# 555_Astable_Multivibrator.net
KiCad netlist of a schematic drawn in Altium Designer
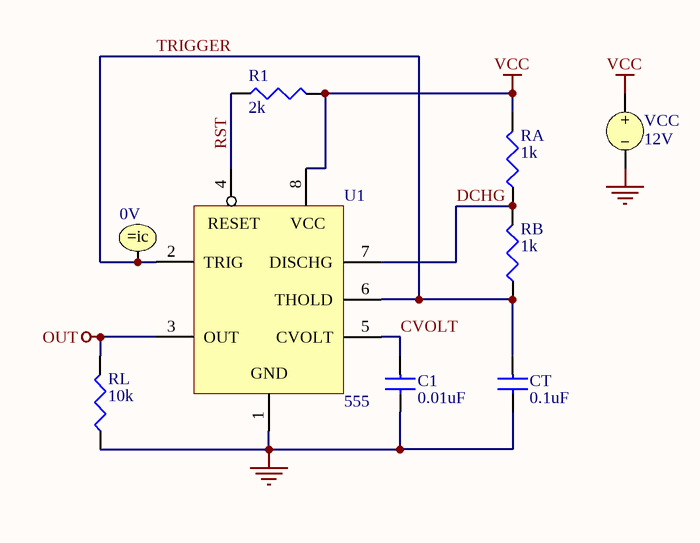
[diagram p0: 555 Astable Multivibrator.schdoc]

(export (version "E")
  (design (tool "Eeschema 10.0.6"))
  (components
    (comp (ref "C1") (value "0.01uF") (description "Capacitor") (libsource (lib "*") (part "CAP")))
    (comp (ref "CT") (value "0.1uF") (description "Capacitor") (libsource (lib "*") (part "CAP")))
    (comp (ref "IC1")
      (value "0V")
      (description "Initial Condition")
      (fields (field (name "INITIAL VOLTAGE") "0V"))
      (libsource (lib "*") (part ".IC"))
    )
    (comp (ref "R1") (value "2k") (description "Resistor") (libsource (lib "*") (part "RES")))
    (comp (ref "RA") (value "1k") (description "Resistor") (libsource (lib "") (part "RES_1")))
    (comp (ref "RB") (value "1k") (description "Resistor") (libsource (lib "") (part "RES_1")))
    (comp (ref "RL") (value "10k") (description "Resistor") (libsource (lib "") (part "RES_1")))
    (comp (ref "U1") (value "555") (description "Timer") (libsource (lib "*") (part "555")))
    (comp (ref "VCC") (value "12V") (description "Voltage Source") (libsource (lib "*") (part "VSRC")))
  )
  (nets
    (net (code "1") (name "/CVOLT") (class "Default")
      (node (ref "C1") (pin "1") (pinfunction "1_1") (pintype "passive"))
      (node (ref "U1") (pin "5") (pinfunction "CVOLT_5") (pintype "passive"))
    )
    (net (code "2") (name "/DCHG") (class "Default")
      (node (ref "RA") (pin "2") (pinfunction "BOT_2") (pintype "passive"))
      (node (ref "RB") (pin "1") (pinfunction "TOP_1") (pintype "passive"))
      (node (ref "U1") (pin "7") (pinfunction "DISCHG_7") (pintype "passive"))
    )
    (net (code "3") (name "/RST") (class "Default")
      (node (ref "R1") (pin "2") (pinfunction "BOT_2") (pintype "passive"))
      (node (ref "U1") (pin "4") (pinfunction "RESET_4") (pintype "passive"))
    )
    (net (code "4") (name "/TRIGGER") (class "Default")
      (node (ref "CT") (pin "1") (pinfunction "1_1") (pintype "passive"))
      (node (ref "IC1") (pin "1") (pinfunction "1_1") (pintype "passive"))
      (node (ref "RB") (pin "2") (pinfunction "BOT_2") (pintype "passive"))
      (node (ref "U1") (pin "2") (pinfunction "TRIG_2") (pintype "passive"))
      (node (ref "U1") (pin "6") (pinfunction "THOLD_6") (pintype "passive"))
    )
    (net (code "5") (name "GND") (class "Default")
      (node (ref "C1") (pin "2") (pinfunction "2_2") (pintype "passive"))
      (node (ref "CT") (pin "2") (pinfunction "2_2") (pintype "passive"))
      (node (ref "RL") (pin "2") (pinfunction "BOT_2") (pintype "passive"))
      (node (ref "U1") (pin "1") (pinfunction "GND_1") (pintype "passive"))
      (node (ref "VCC") (pin "2") (pinfunction "2_2") (pintype "passive"))
    )
    (net (code "6") (name "OUT") (class "Default")
      (node (ref "RL") (pin "1") (pinfunction "TOP_1") (pintype "passive"))
      (node (ref "U1") (pin "3") (pinfunction "OUT_3") (pintype "passive"))
    )
    (net (code "7") (name "VCC") (class "Default")
      (node (ref "R1") (pin "1") (pinfunction "TOP_1") (pintype "passive"))
      (node (ref "RA") (pin "1") (pinfunction "TOP_1") (pintype "passive"))
      (node (ref "U1") (pin "8") (pinfunction "VCC_8") (pintype "passive"))
      (node (ref "VCC") (pin "1") (pinfunction "1_1") (pintype "passive"))
    )
  )
)
